# BatteryManagementSystem.net
KiCad netlist of a schematic drawn in Altium Designer
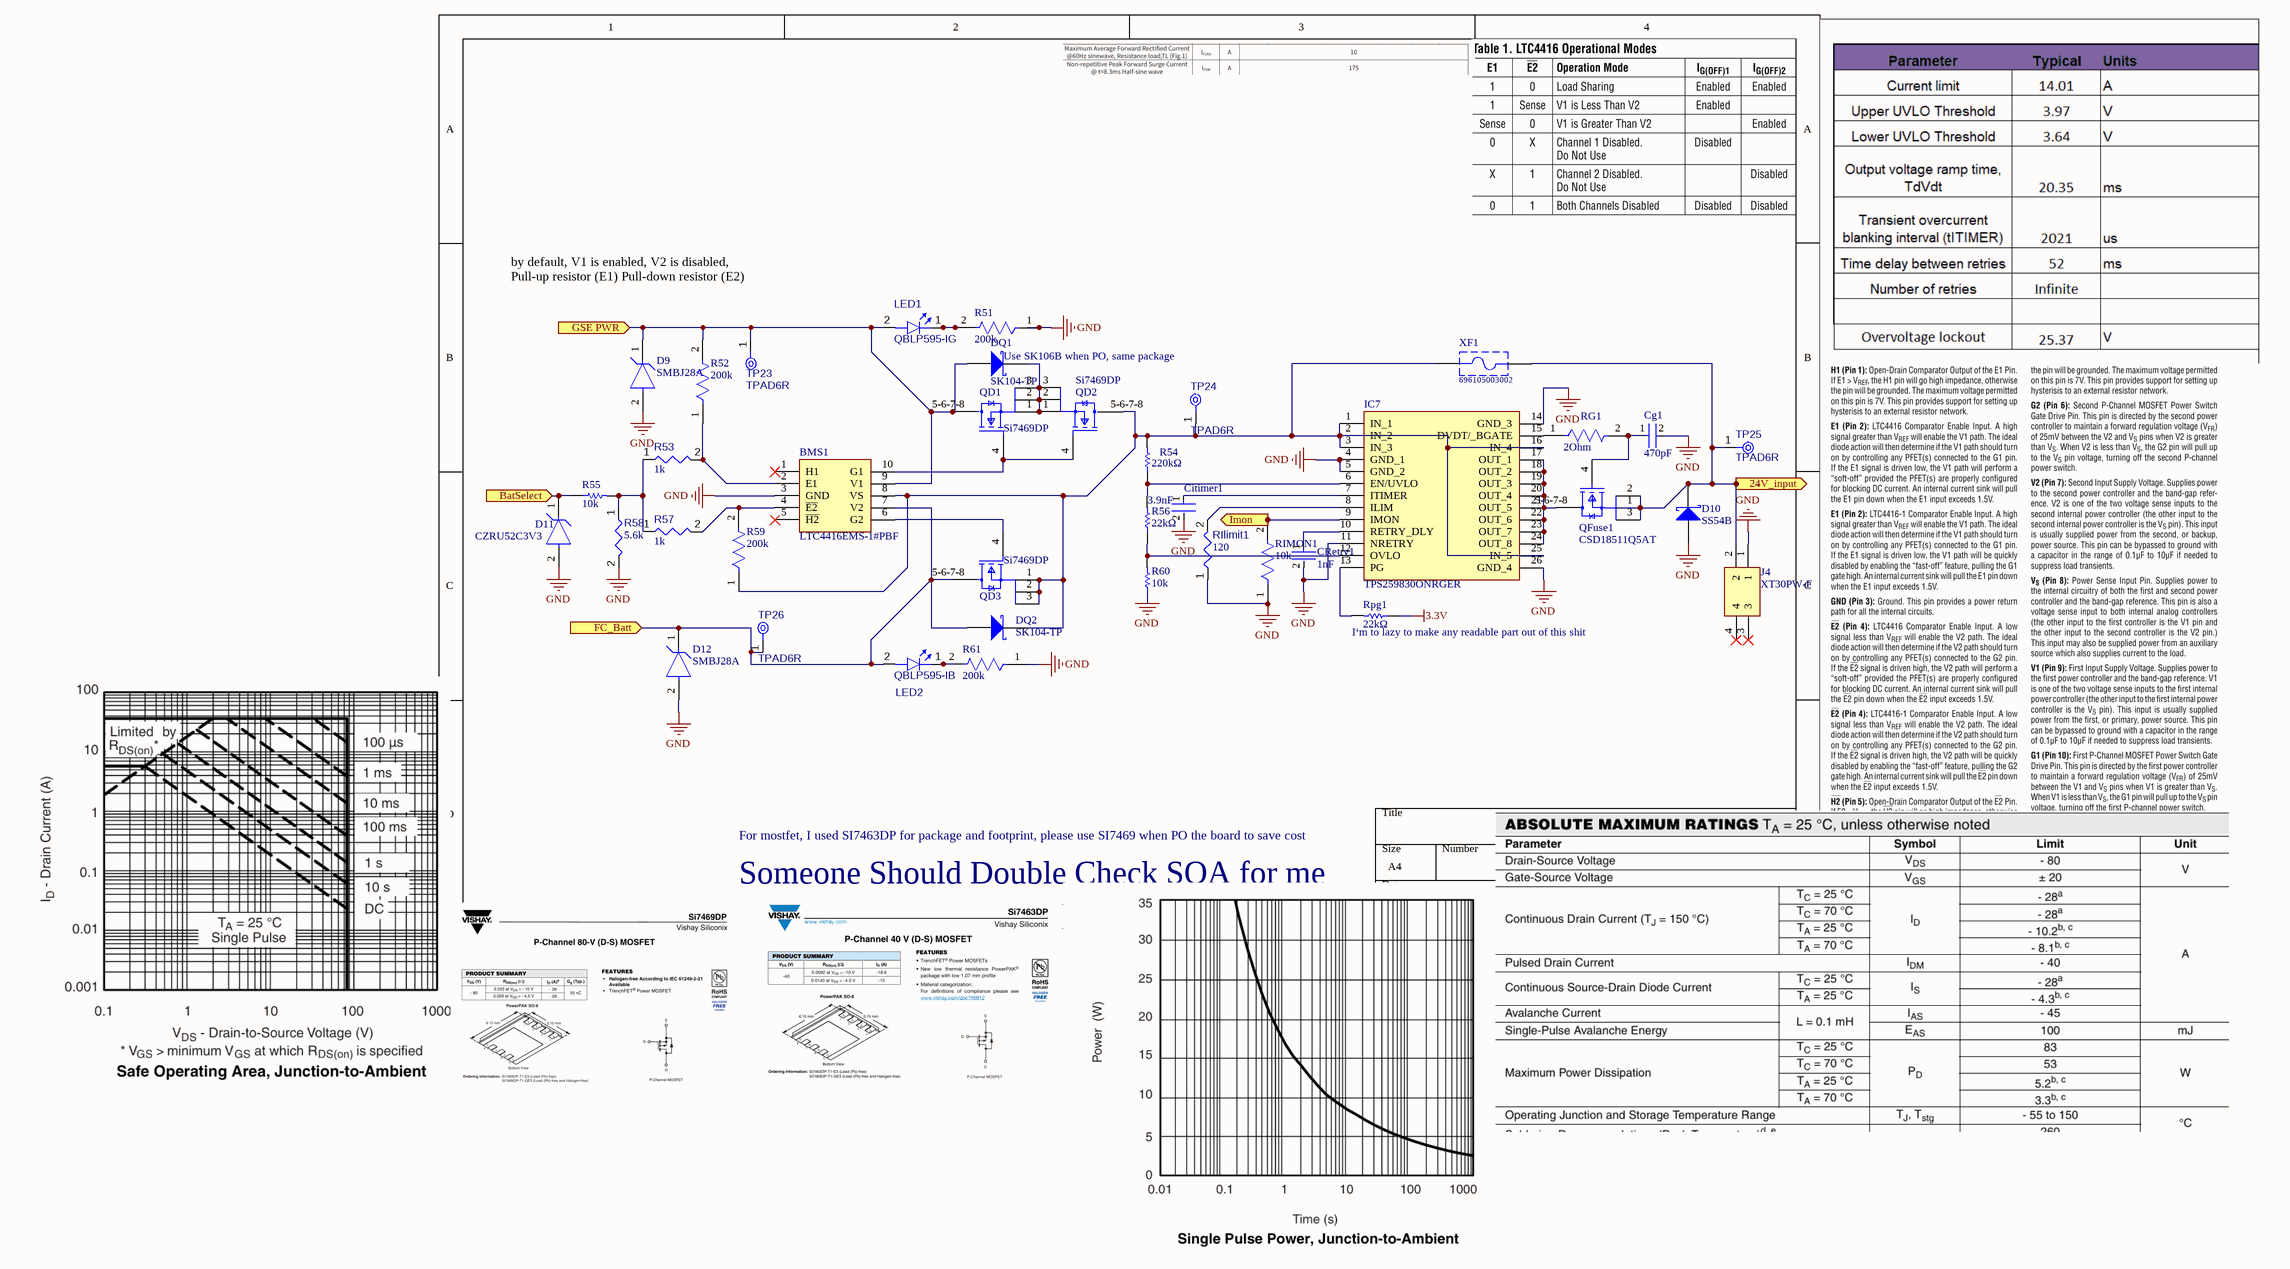
[diagram p0: BatteryManagementSystem.SchDoc]

(export (version "E")
  (design (tool "Eeschema 10.0.6"))
  (components
    (comp (ref "BMS1")
      (value "LTC4416EMS-1#PBF")
      (footprint "SamacSys:SOP50P490X110-10N")
      (description "Integrated Circuit")
      (fields (field (name "MOUSER PART NUMBER") "584-LTC4416EMS-1#PBF"))
      (libsource (lib "*") (part "LTC4416EMS-1#PBF"))
    )
    (comp (ref "Cg1")
      (value "470pF")
      (footprint "FP-CC0603-DA-MFG")
      (description "CAP CER 470pF 50V X7R 0603")
      (fields (field (name "TOLERANCE") "10%") (field (name "VOLTAGE") "50V"))
      (libsource (lib "Altium Content Vault") (part "11868f565c42a9108669ba33697ecf6"))
    )
    (comp (ref "Citimer1")
      (value "3.9nF")
      (footprint "FP-CC0603-DA-MFG")
      (description "CAP CER 3900PF 50V X7R 0603")
      (fields (field (name "TOLERANCE") "10%") (field (name "VOLTAGE") "50V"))
      (libsource (lib "Altium Content Vault") (part "11868f565c42a9108669ba33697ecf6"))
    )
    (comp (ref "CRetry1")
      (value "1nF")
      (footprint "FP-0603-L_1_6_0_15-W_0_81-IPC_A")
      (description "General Purpose Ceramic Capacitor, 0603, 1nF, 10%, X7R, 15%, 50V")
      (fields (field (name "VOLTAGE") "50V") (field (name "TOLERANCE") "10%"))
      (libsource (lib "Altium Content Vault") (part "02cd4be3c70576c341d710602a673aa"))
    )
    (comp (ref "D9")
      (value "SMBJ28A")
      (footprint "FP-SMBJ-MFG")
      (description "TVS DIODE 28V 45.4V DO214AA")
      (fields
        (field (name "MANUFACTURER") "Littelfuse Inc")
        (field (name "OCTOPART") "https://octopart.com/smbj28a-littelfuse-350790")
      )
      (libsource (lib "Altium Content Vault") (part "f813f71cba58e380607f5dd3caf9714"))
    )
    (comp (ref "D10")
      (value "SS54B")
      (footprint "JCET-SMB-2_M")
      (description "Schottky Barrier Rectifier, 40 V, 5 A, -55 to 150 degC, 2-Pin SMD")
      (fields (field (name "MANUFACTURER") "JCET"))
      (libsource (lib "Yuxuan chen") (part "DSKY-AK-2"))
    )
    (comp (ref "D11")
      (value "CZRU52C3V3")
      (footprint "FP-0603-SOD-523F-MFG")
      (description "DIODE ZENER 3.3V 150MW 0603")
      (fields (field (name "TOLERANCE") "5%"))
      (libsource (lib "Altium Content Vault") (part "f813f71cba58e380607f5dd3caf9714"))
    )
    (comp (ref "D12")
      (value "SMBJ28A")
      (footprint "FP-SMBJ-MFG")
      (description "TVS DIODE 28V 45.4V DO214AA")
      (fields
        (field (name "MANUFACTURER") "Littelfuse Inc")
        (field (name "OCTOPART") "https://octopart.com/smbj28a-littelfuse-350790")
      )
      (libsource (lib "Altium Content Vault") (part "f813f71cba58e380607f5dd3caf9714"))
    )
    (comp (ref "DQ1")
      (value "SK104-TP")
      (footprint "MCC-DO-214AB-2_V")
      (description "Schottky Rectifier, 40 V, 10 A, -55 to 125 degC, 2-Pin SMD, RoHS, Tape and Reel")
      (fields (field (name "MANUFACTURER") "Micro Commercial Components"))
      (libsource (lib "Altium Content Vault") (part "DSKY-AK-2"))
    )
    (comp (ref "DQ2")
      (value "SK104-TP")
      (footprint "MCC-DO-214AB-2_V")
      (description "Schottky Rectifier, 40 V, 10 A, -55 to 125 degC, 2-Pin SMD, RoHS, Tape and Reel")
      (fields (field (name "MANUFACTURER") "Micro Commercial Components"))
      (libsource (lib "Altium Content Vault") (part "DSKY-AK-2"))
    )
    (comp (ref "IC7")
      (value "TPS259830ONRGER")
      (footprint "SamacSys:TPS259830ONRGER")
      (description "Integrated Circuit")
      (fields (field (name "MOUSER PART NUMBER") "595-TPS259830ONRGER"))
      (libsource (lib "*") (part "TPS259830ONRGER"))
    )
    (comp (ref "J4")
      (value "XT30PW-F")
      (footprint "SamacSys:XT30PWF")
      (description "Connector")
      (libsource (lib "*") (part "XT30PW-F"))
    )
    (comp (ref "LED1")
      (value "QBLP595-IG")
      (footprint "QTB-QBLP595_V")
      (description "Chip LED 0402, Green, 0.02 A, 3.1 to 3.7 V, -40 to 80 degC, 2-Pin SMD, RoHS, Tape and Reel")
      (libsource (lib "Yuxuan chen") (part "LED-KA-2"))
    )
    (comp (ref "LED2")
      (value "QBLP595-IB")
      (footprint "QTB-QBLP595_V")
      (description "Chip LED 0402, Blue, 0.02 A, 3.1 to 3.7 V, -40 to 80 degC, 2-Pin SMD, RoHS, Tape and Reel")
      (libsource (lib "Yuxuan chen") (part "LED-KA-2"))
    )
    (comp (ref "QD1")
      (value "Si7469DP")
      (footprint "FP-S17-0173-SINGLE-MFG")
      (description "Use Si7469DP For PCBA. MOSFET P-CH 40V 11A PPAK SO-8")
      (fields
        (field (name "MANUFACTURER") "Vishay")
        (field (name "OCTOPART") "https://octopart.com/si7463dp-t1-e3-vishay-42065245")
      )
      (libsource (lib "Altium Content Vault") (part "b7bcde56cf7e2f7a604793c3855a7b6"))
    )
    (comp (ref "QD2")
      (value "Si7469DP")
      (footprint "FP-S17-0173-SINGLE-MFG")
      (description "MOSFET P-CH 40V 11A PPAK SO-8")
      (fields
        (field (name "MANUFACTURER") "Vishay")
        (field (name "OCTOPART") "https://octopart.com/si7463dp-t1-e3-vishay-42065245")
      )
      (libsource (lib "Altium Content Vault") (part "b7bcde56cf7e2f7a604793c3855a7b6"))
    )
    (comp (ref "QD3")
      (value "Si7469DP")
      (footprint "FP-S17-0173-SINGLE-MFG")
      (description "Use Si7469DP For PCBA. MOSFET P-CH 40V 11A PPAK SO-8")
      (fields
        (field (name "MANUFACTURER") "Vishay")
        (field (name "OCTOPART") "https://octopart.com/si7463dp-t1-e3-vishay-42065245")
      )
      (libsource (lib "Altium Content Vault") (part "b7bcde56cf7e2f7a604793c3855a7b6"))
    )
    (comp (ref "QFuse1")
      (value "CSD18511Q5AT")
      (footprint "FP-DQJ0008A-MFG")
      (description "MOSFET N-CH 40V 159A 8VSON")
      (libsource (lib "Altium Content Vault") (part "85b2916a9e5398a3ffab9af6f2a2403"))
    )
    (comp (ref "R51")
      (value "200k")
      (footprint "FP-RC0603-0_55-IPC_B")
      (description "RES SMD 200K OHM 1% 1/10W 0603")
      (fields (field (name "TOLERANCE") "1%"))
      (libsource (lib "Altium Content Vault") (part "1029c3af85768c4190bb7ad29bc67b5"))
    )
    (comp (ref "R52")
      (value "200k")
      (footprint "FP-RC0603-0_55-IPC_B")
      (description "RES SMD 200K OHM 1% 1/10W 0603")
      (fields (field (name "TOLERANCE") "1%"))
      (libsource (lib "Altium Content Vault") (part "1029c3af85768c4190bb7ad29bc67b5"))
    )
    (comp (ref "R53")
      (value "1k")
      (footprint "RESC1608X55X25ML10T15")
      (description "Chip Resistor, 1 KOhm, +/-1%, 0.1 W, -55 to 155 degC, 0603 (1608 Metric)")
      (fields (field (name "POWER") "100mW") (field (name "TOLERANCE") "1%"))
      (libsource (lib "Yuxuan chen") (part "RES-2"))
    )
    (comp (ref "R54")
      (value "220kΩ")
      (footprint "RESC1608X55X30ML20T20")
      (description "Fixed Resistor, Thin Film, 0.1W, 210000ohm, 75V, 0.1% +/-Tol, 25ppm/Cel, Surface Mount, 0603")
      (fields (field (name "PART NUMBER") "ERA3AEB392V") (field (name "MANUFACTURER") "Panasonic"))
      (libsource (lib "Altium Content Vault") (part "RES"))
    )
    (comp (ref "R55")
      (value "10k")
      (footprint "RESC1609X55X30LL15T15")
      (description "Chip Resistor, 10 KOhm, +/- 1%, 0.1 W, -55 to 155 degC, 0603 (1608 Metric), RoHS, Tape and Reel")
      (fields (field (name "TOLERANCE") "1%") (field (name "MANUFACTURER") "Panasonic"))
      (libsource (lib "Altium Content Vault") (part "RES-2"))
    )
    (comp (ref "R56")
      (value "22kΩ")
      (footprint "RESC1609X50X30ML10T20")
      (fields (field (name "PART NUMBER") "CRCW0603182KFKEA") (field (name "MANUFACTURER") "Vishay Dale"))
      (libsource (lib "Altium Content Vault") (part "RES"))
    )
    (comp (ref "R57")
      (value "1k")
      (footprint "RESC1608X55X25ML10T15")
      (description "Chip Resistor, 1 KOhm, +/-1%, 0.1 W, -55 to 155 degC, 0603 (1608 Metric)")
      (fields (field (name "POWER") "100mW") (field (name "TOLERANCE") "1%"))
      (libsource (lib "Yuxuan chen") (part "RES-2"))
    )
    (comp (ref "R58")
      (value "5.6k")
      (footprint "RESC1608X55X25ML10T15")
      (description "Chip Resistor, 10 KOhm, +/- 1%, 01 W, -55 to 155 degC, 0603 (1608 Metric)")
      (fields (field (name "POWER") "100mW") (field (name "TOLERANCE") "1%"))
      (libsource (lib "Charlie's Workspace") (part "RES-2"))
    )
    (comp (ref "R59")
      (value "200k")
      (footprint "FP-RC0603-0_55-IPC_B")
      (description "RES SMD 200K OHM 1% 1/10W 0603")
      (fields (field (name "TOLERANCE") "1%"))
      (libsource (lib "Altium Content Vault") (part "1029c3af85768c4190bb7ad29bc67b5"))
    )
    (comp (ref "R60")
      (value "10k")
      (footprint "RESC1609X55X30LL15T15")
      (description "Chip Resistor, 10 KOhm, +/- 1%, 0.1 W, -55 to 155 degC, 0603 (1608 Metric), RoHS, Tape and Reel")
      (fields (field (name "TOLERANCE") "1%") (field (name "MANUFACTURER") "Panasonic"))
      (libsource (lib "Altium Content Vault") (part "RES-2"))
    )
    (comp (ref "R61")
      (value "200k")
      (footprint "FP-RC0603-0_55-IPC_B")
      (description "RES SMD 200K OHM 1% 1/10W 0603")
      (fields (field (name "TOLERANCE") "1%"))
      (libsource (lib "Altium Content Vault") (part "1029c3af85768c4190bb7ad29bc67b5"))
    )
    (comp (ref "RG1")
      (value "2Ohm")
      (footprint "FP-CRCW2512-e3-IPC_C")
      (description "RES Thick Film, 2Ω, 5%, 1W, 200ppm/°C, 2512")
      (fields (field (name "TOLERANCE") "5%"))
      (libsource (lib "Altium Content Vault") (part "1029c3af85768c4190bb7ad29bc67b5"))
    )
    (comp (ref "RIlimit1")
      (value "120")
      (footprint "RESC0603(1608)_L")
      (description "Chip Resistor, 120 Ohms, +/-5 %, 0.1 W, -55 to 155 degC, 0603")
      (fields (field (name "POWER") "100mW") (field (name "TOLERANCE") "5%"))
      (libsource (lib "Yuxuan chen") (part "RES-2"))
    )
    (comp (ref "RIMON1")
      (value "10k")
      (footprint "FP-CRCW0805-e3-IPC_A")
      (description "RES Thick Film, 10kΩ, 1%, 0.125W, 100ppm/°C, 0805")
      (fields (field (name "TOLERANCE") "1%"))
      (libsource (lib "Altium Content Vault") (part "1029c3af85768c4190bb7ad29bc67b5"))
    )
    (comp (ref "Rpg1")
      (value "22kΩ")
      (footprint "RESC1609X50X30ML10T20")
      (fields (field (name "PART NUMBER") "CRCW0603182KFKEA") (field (name "MANUFACTURER") "Vishay Dale"))
      (libsource (lib "Altium Content Vault") (part "RES"))
    )
    (comp (ref "TP23")
      (value "TPAD6R")
      (footprint "TP06R")
      (description "0.6mm round")
      (libsource (lib "Yuxuan chen") (part "CMP-001-0001-4"))
    )
    (comp (ref "TP24")
      (value "TPAD6R")
      (footprint "TP06R")
      (description "0.6mm round")
      (libsource (lib "Yuxuan chen") (part "CMP-001-0001-4"))
    )
    (comp (ref "TP25")
      (value "TPAD6R")
      (footprint "TP06R")
      (description "0.6mm round")
      (libsource (lib "Yuxuan chen") (part "CMP-001-0001-4"))
    )
    (comp (ref "TP26")
      (value "TPAD6R")
      (footprint "TP06R")
      (description "0.6mm round")
      (libsource (lib "Yuxuan chen") (part "CMP-001-0001-4"))
    )
    (comp (ref "XF1")
      (value "696105003002")
      (footprint "696105003002")
      (description "WR-FSH Fuse Holder Blocks Fuse Holder Blocks Clip Cover for PCB")
      (fields (field (name "MANUFACTURER") "Wurth Elektronik") (field (name "PUBLISHER") "WurthElektronik"))
      (libsource (lib "Altium Content Vault") (part "WE-FUSE-2"))
    )
  )
  (nets
    (net (code "1") (name "/24V_input") (class "Default")
      (node (ref "D10") (pin "2") (pinfunction "K_2") (pintype "passive"))
      (node (ref "J4") (pin "2") (pinfunction "2_2") (pintype "passive"))
      (node (ref "QFuse1") (pin "1") (pinfunction "S_1") (pintype "passive"))
      (node (ref "QFuse1") (pin "2") (pinfunction "S_2") (pintype "passive"))
      (node (ref "QFuse1") (pin "3") (pinfunction "S_3") (pintype "passive"))
      (node (ref "TP25") (pin "1") (pinfunction "TP_1") (pintype "passive"))
      (node (ref "XF1") (pin "2") (pinfunction "2_2") (pintype "passive"))
    )
    (net (code "2") (name "/BatSelect") (class "Default")
      (node (ref "D11") (pin "1") (pinfunction "C_1") (pintype "passive"))
      (node (ref "R55") (pin "1") (pinfunction "1_1") (pintype "passive"))
    )
    (net (code "3") (name "/FC_Batt") (class "Default")
      (node (ref "BMS1") (pin "7") (pinfunction "V2_7") (pintype "passive"))
      (node (ref "D12") (pin "1") (pinfunction "C_1") (pintype "passive"))
      (node (ref "DQ2") (pin "1") (pinfunction "A_1") (pintype "passive"))
      (node (ref "LED2") (pin "2") (pinfunction "A_2") (pintype "passive"))
      (node (ref "QD3") (pin "5-6-7-8") (pinfunction "D_5-6-7-8") (pintype "passive"))
      (node (ref "TP26") (pin "1") (pinfunction "TP_1") (pintype "passive"))
    )
    (net (code "4") (name "/GSE PWR") (class "Default")
      (node (ref "BMS1") (pin "9") (pinfunction "V1_9") (pintype "passive"))
      (node (ref "D9") (pin "1") (pinfunction "C_1") (pintype "passive"))
      (node (ref "DQ1") (pin "1") (pinfunction "A_1") (pintype "passive"))
      (node (ref "LED1") (pin "2") (pinfunction "A_2") (pintype "passive"))
      (node (ref "QD1") (pin "5-6-7-8") (pinfunction "D_5-6-7-8") (pintype "passive"))
      (node (ref "R52") (pin "2") (pinfunction "2_2") (pintype "passive"))
      (node (ref "TP23") (pin "1") (pinfunction "TP_1") (pintype "passive"))
    )
    (net (code "5") (name "/Imon") (class "Default")
      (node (ref "IC7") (pin "9") (pinfunction "IMON_9") (pintype "passive"))
      (node (ref "RIMON1") (pin "2") (pinfunction "2_2") (pintype "passive"))
    )
    (net (code "6") (name "3.3V") (class "Default")
      (node (ref "Rpg1") (pin "1") (pinfunction "1_1") (pintype "passive"))
    )
    (net (code "7") (name "GND") (class "Default")
      (node (ref "BMS1") (pin "3") (pinfunction "GND_3") (pintype "passive"))
      (node (ref "CRetry1") (pin "2") (pinfunction "2_2") (pintype "passive"))
      (node (ref "Cg1") (pin "2") (pinfunction "2_2") (pintype "passive"))
      (node (ref "Citimer1") (pin "2") (pinfunction "2_2") (pintype "passive"))
      (node (ref "D10") (pin "1") (pinfunction "A_1") (pintype "passive"))
      (node (ref "D11") (pin "2") (pinfunction "A_2") (pintype "passive"))
      (node (ref "D12") (pin "2") (pinfunction "A_2") (pintype "passive"))
      (node (ref "D9") (pin "2") (pinfunction "A_2") (pintype "passive"))
      (node (ref "IC7") (pin "11") (pinfunction "NRETRY_11") (pintype "passive"))
      (node (ref "IC7") (pin "14") (pinfunction "GND_3_14") (pintype "passive"))
      (node (ref "IC7") (pin "26") (pinfunction "GND_4_26") (pintype "passive"))
      (node (ref "IC7") (pin "4") (pinfunction "GND_1_4") (pintype "passive"))
      (node (ref "IC7") (pin "5") (pinfunction "GND_2_5") (pintype "passive"))
      (node (ref "J4") (pin "1") (pinfunction "1_1") (pintype "passive"))
      (node (ref "R51") (pin "1") (pinfunction "1_1") (pintype "passive"))
      (node (ref "R58") (pin "2") (pinfunction "2_2") (pintype "passive"))
      (node (ref "R60") (pin "1") (pinfunction "1_1") (pintype "passive"))
      (node (ref "R61") (pin "1") (pinfunction "1_1") (pintype "passive"))
      (node (ref "RIMON1") (pin "1") (pinfunction "1_1") (pintype "passive"))
      (node (ref "RIlimit1") (pin "1") (pinfunction "1_1") (pintype "passive"))
    )
    (net (code "8") (name "Net-(BMS1-E1)") (class "Default")
      (node (ref "BMS1") (pin "2") (pinfunction "E1_2") (pintype "passive"))
      (node (ref "R52") (pin "1") (pinfunction "1_1") (pintype "passive"))
      (node (ref "R53") (pin "2") (pinfunction "2_2") (pintype "passive"))
    )
    (net (code "9") (name "Net-(BMS1-G1)") (class "Default")
      (node (ref "BMS1") (pin "10") (pinfunction "G1_10") (pintype "passive"))
      (node (ref "QD1") (pin "4") (pinfunction "G_4") (pintype "passive"))
      (node (ref "QD2") (pin "4") (pinfunction "G_4") (pintype "passive"))
    )
    (net (code "10") (name "Net-(BMS1-G2)") (class "Default")
      (node (ref "BMS1") (pin "6") (pinfunction "G2_6") (pintype "passive"))
      (node (ref "QD3") (pin "4") (pinfunction "G_4") (pintype "passive"))
    )
    (net (code "11") (name "Net-(BMS1-VS)") (class "Default")
      (node (ref "BMS1") (pin "8") (pinfunction "VS_8") (pintype "passive"))
      (node (ref "DQ2") (pin "2") (pinfunction "K_2") (pintype "passive"))
      (node (ref "IC7") (pin "1") (pinfunction "IN_1_1") (pintype "passive"))
      (node (ref "IC7") (pin "16") (pinfunction "IN_4_16") (pintype "passive"))
      (node (ref "IC7") (pin "2") (pinfunction "IN_2_2") (pintype "passive"))
      (node (ref "IC7") (pin "25") (pinfunction "IN_5_25") (pintype "passive"))
      (node (ref "IC7") (pin "3") (pinfunction "IN_3_3") (pintype "passive"))
      (node (ref "QD2") (pin "5-6-7-8") (pinfunction "D_5-6-7-8") (pintype "passive"))
      (node (ref "QD3") (pin "1") (pinfunction "S_1") (pintype "passive"))
      (node (ref "QD3") (pin "2") (pinfunction "S_2") (pintype "passive"))
      (node (ref "QD3") (pin "3") (pinfunction "S_3") (pintype "passive"))
      (node (ref "R54") (pin "2") (pinfunction "2_2") (pintype "passive"))
      (node (ref "R59") (pin "1") (pinfunction "1_1") (pintype "passive"))
      (node (ref "TP24") (pin "1") (pinfunction "TP_1") (pintype "passive"))
      (node (ref "XF1") (pin "1") (pinfunction "1_1") (pintype "passive"))
    )
    (net (code "12") (name "Net-(BMS1-~{E2})") (class "Default")
      (node (ref "BMS1") (pin "4") (pinfunction "~{E2}_4") (pintype "passive"))
      (node (ref "R57") (pin "2") (pinfunction "2_2") (pintype "passive"))
      (node (ref "R59") (pin "2") (pinfunction "2_2") (pintype "passive"))
    )
    (net (code "13") (name "Net-(DQ1-K)") (class "Default")
      (node (ref "DQ1") (pin "2") (pinfunction "K_2") (pintype "passive"))
      (node (ref "QD1") (pin "1") (pinfunction "S_1") (pintype "passive"))
      (node (ref "QD1") (pin "2") (pinfunction "S_2") (pintype "passive"))
      (node (ref "QD1") (pin "3") (pinfunction "S_3") (pintype "passive"))
      (node (ref "QD2") (pin "1") (pinfunction "S_1") (pintype "passive"))
      (node (ref "QD2") (pin "2") (pinfunction "S_2") (pintype "passive"))
      (node (ref "QD2") (pin "3") (pinfunction "S_3") (pintype "passive"))
    )
    (net (code "14") (name "Net-(IC7-DVDT{slash}_BGATE)") (class "Default")
      (node (ref "IC7") (pin "15") (pinfunction "DVDT/_BGATE_15") (pintype "passive"))
      (node (ref "RG1") (pin "1") (pinfunction "1_1") (pintype "passive"))
    )
    (net (code "15") (name "Net-(IC7-EN{slash}UVLO)") (class "Default")
      (node (ref "IC7") (pin "6") (pinfunction "EN/UVLO_6") (pintype "passive"))
      (node (ref "R54") (pin "1") (pinfunction "1_1") (pintype "passive"))
      (node (ref "R56") (pin "2") (pinfunction "2_2") (pintype "passive"))
    )
    (net (code "16") (name "Net-(IC7-ILIM)") (class "Default")
      (node (ref "IC7") (pin "8") (pinfunction "ILIM_8") (pintype "passive"))
      (node (ref "RIlimit1") (pin "2") (pinfunction "2_2") (pintype "passive"))
    )
    (net (code "17") (name "Net-(IC7-ITIMER)") (class "Default")
      (node (ref "Citimer1") (pin "1") (pinfunction "1_1") (pintype "passive"))
      (node (ref "IC7") (pin "7") (pinfunction "ITIMER_7") (pintype "passive"))
    )
    (net (code "18") (name "Net-(IC7-OUT_1)") (class "Default")
      (node (ref "IC7") (pin "17") (pinfunction "OUT_1_17") (pintype "passive"))
      (node (ref "IC7") (pin "18") (pinfunction "OUT_2_18") (pintype "passive"))
      (node (ref "IC7") (pin "19") (pinfunction "OUT_3_19") (pintype "passive"))
      (node (ref "IC7") (pin "20") (pinfunction "OUT_4_20") (pintype "passive"))
      (node (ref "IC7") (pin "21") (pinfunction "OUT_5_21") (pintype "passive"))
      (node (ref "IC7") (pin "22") (pinfunction "OUT_6_22") (pintype "passive"))
      (node (ref "IC7") (pin "23") (pinfunction "OUT_7_23") (pintype "passive"))
      (node (ref "IC7") (pin "24") (pinfunction "OUT_8_24") (pintype "passive"))
      (node (ref "QFuse1") (pin "5-6-7-8") (pinfunction "D_5-6-7-8") (pintype "passive"))
    )
    (net (code "19") (name "Net-(IC7-OVLO)") (class "Default")
      (node (ref "IC7") (pin "12") (pinfunction "OVLO_12") (pintype "passive"))
      (node (ref "R56") (pin "1") (pinfunction "1_1") (pintype "passive"))
      (node (ref "R60") (pin "2") (pinfunction "2_2") (pintype "passive"))
    )
    (net (code "20") (name "Net-(IC7-PG)") (class "Default")
      (node (ref "IC7") (pin "13") (pinfunction "PG_13") (pintype "passive"))
      (node (ref "Rpg1") (pin "2") (pinfunction "2_2") (pintype "passive"))
    )
    (net (code "21") (name "Net-(IC7-RETRY_DLY)") (class "Default")
      (node (ref "CRetry1") (pin "1") (pinfunction "1_1") (pintype "passive"))
      (node (ref "IC7") (pin "10") (pinfunction "RETRY_DLY_10") (pintype "passive"))
    )
    (net (code "22") (name "Net-(LED1-K)") (class "Default")
      (node (ref "LED1") (pin "1") (pinfunction "K_1") (pintype "passive"))
      (node (ref "R51") (pin "2") (pinfunction "2_2") (pintype "passive"))
    )
    (net (code "23") (name "Net-(LED2-K)") (class "Default")
      (node (ref "LED2") (pin "1") (pinfunction "K_1") (pintype "passive"))
      (node (ref "R61") (pin "2") (pinfunction "2_2") (pintype "passive"))
    )
    (net (code "24") (name "Net-(QFuse1-G)") (class "Default")
      (node (ref "Cg1") (pin "1") (pinfunction "1_1") (pintype "passive"))
      (node (ref "QFuse1") (pin "4") (pinfunction "G_4") (pintype "passive"))
      (node (ref "RG1") (pin "2") (pinfunction "2_2") (pintype "passive"))
    )
    (net (code "25") (name "Net-(R53-Pad1)") (class "Default")
      (node (ref "R53") (pin "1") (pinfunction "1_1") (pintype "passive"))
      (node (ref "R55") (pin "2") (pinfunction "2_2") (pintype "passive"))
      (node (ref "R57") (pin "1") (pinfunction "1_1") (pintype "passive"))
      (node (ref "R58") (pin "1") (pinfunction "1_1") (pintype "passive"))
    )
    (net (code "26") (name "unconnected-(BMS1-H1-Pad1)") (class "Default")
      (node (ref "BMS1") (pin "1") (pinfunction "H1_1") (pintype "passive+no_connect"))
    )
    (net (code "27") (name "unconnected-(BMS1-~{H2}-Pad5)") (class "Default")
      (node (ref "BMS1") (pin "5") (pinfunction "~{H2}_5") (pintype "passive+no_connect"))
    )
    (net (code "28") (name "unconnected-(J4-Pad3)") (class "Default")
      (node (ref "J4") (pin "3") (pinfunction "3_3") (pintype "passive+no_connect"))
    )
    (net (code "29") (name "unconnected-(J4-Pad4)") (class "Default")
      (node (ref "J4") (pin "4") (pinfunction "4_4") (pintype "passive+no_connect"))
    )
  )
)
